# SCH_Flexihal_Direct-Plug_Driver_to_RJ45_.net
KiCad netlist of a schematic drawn in EasyEDA
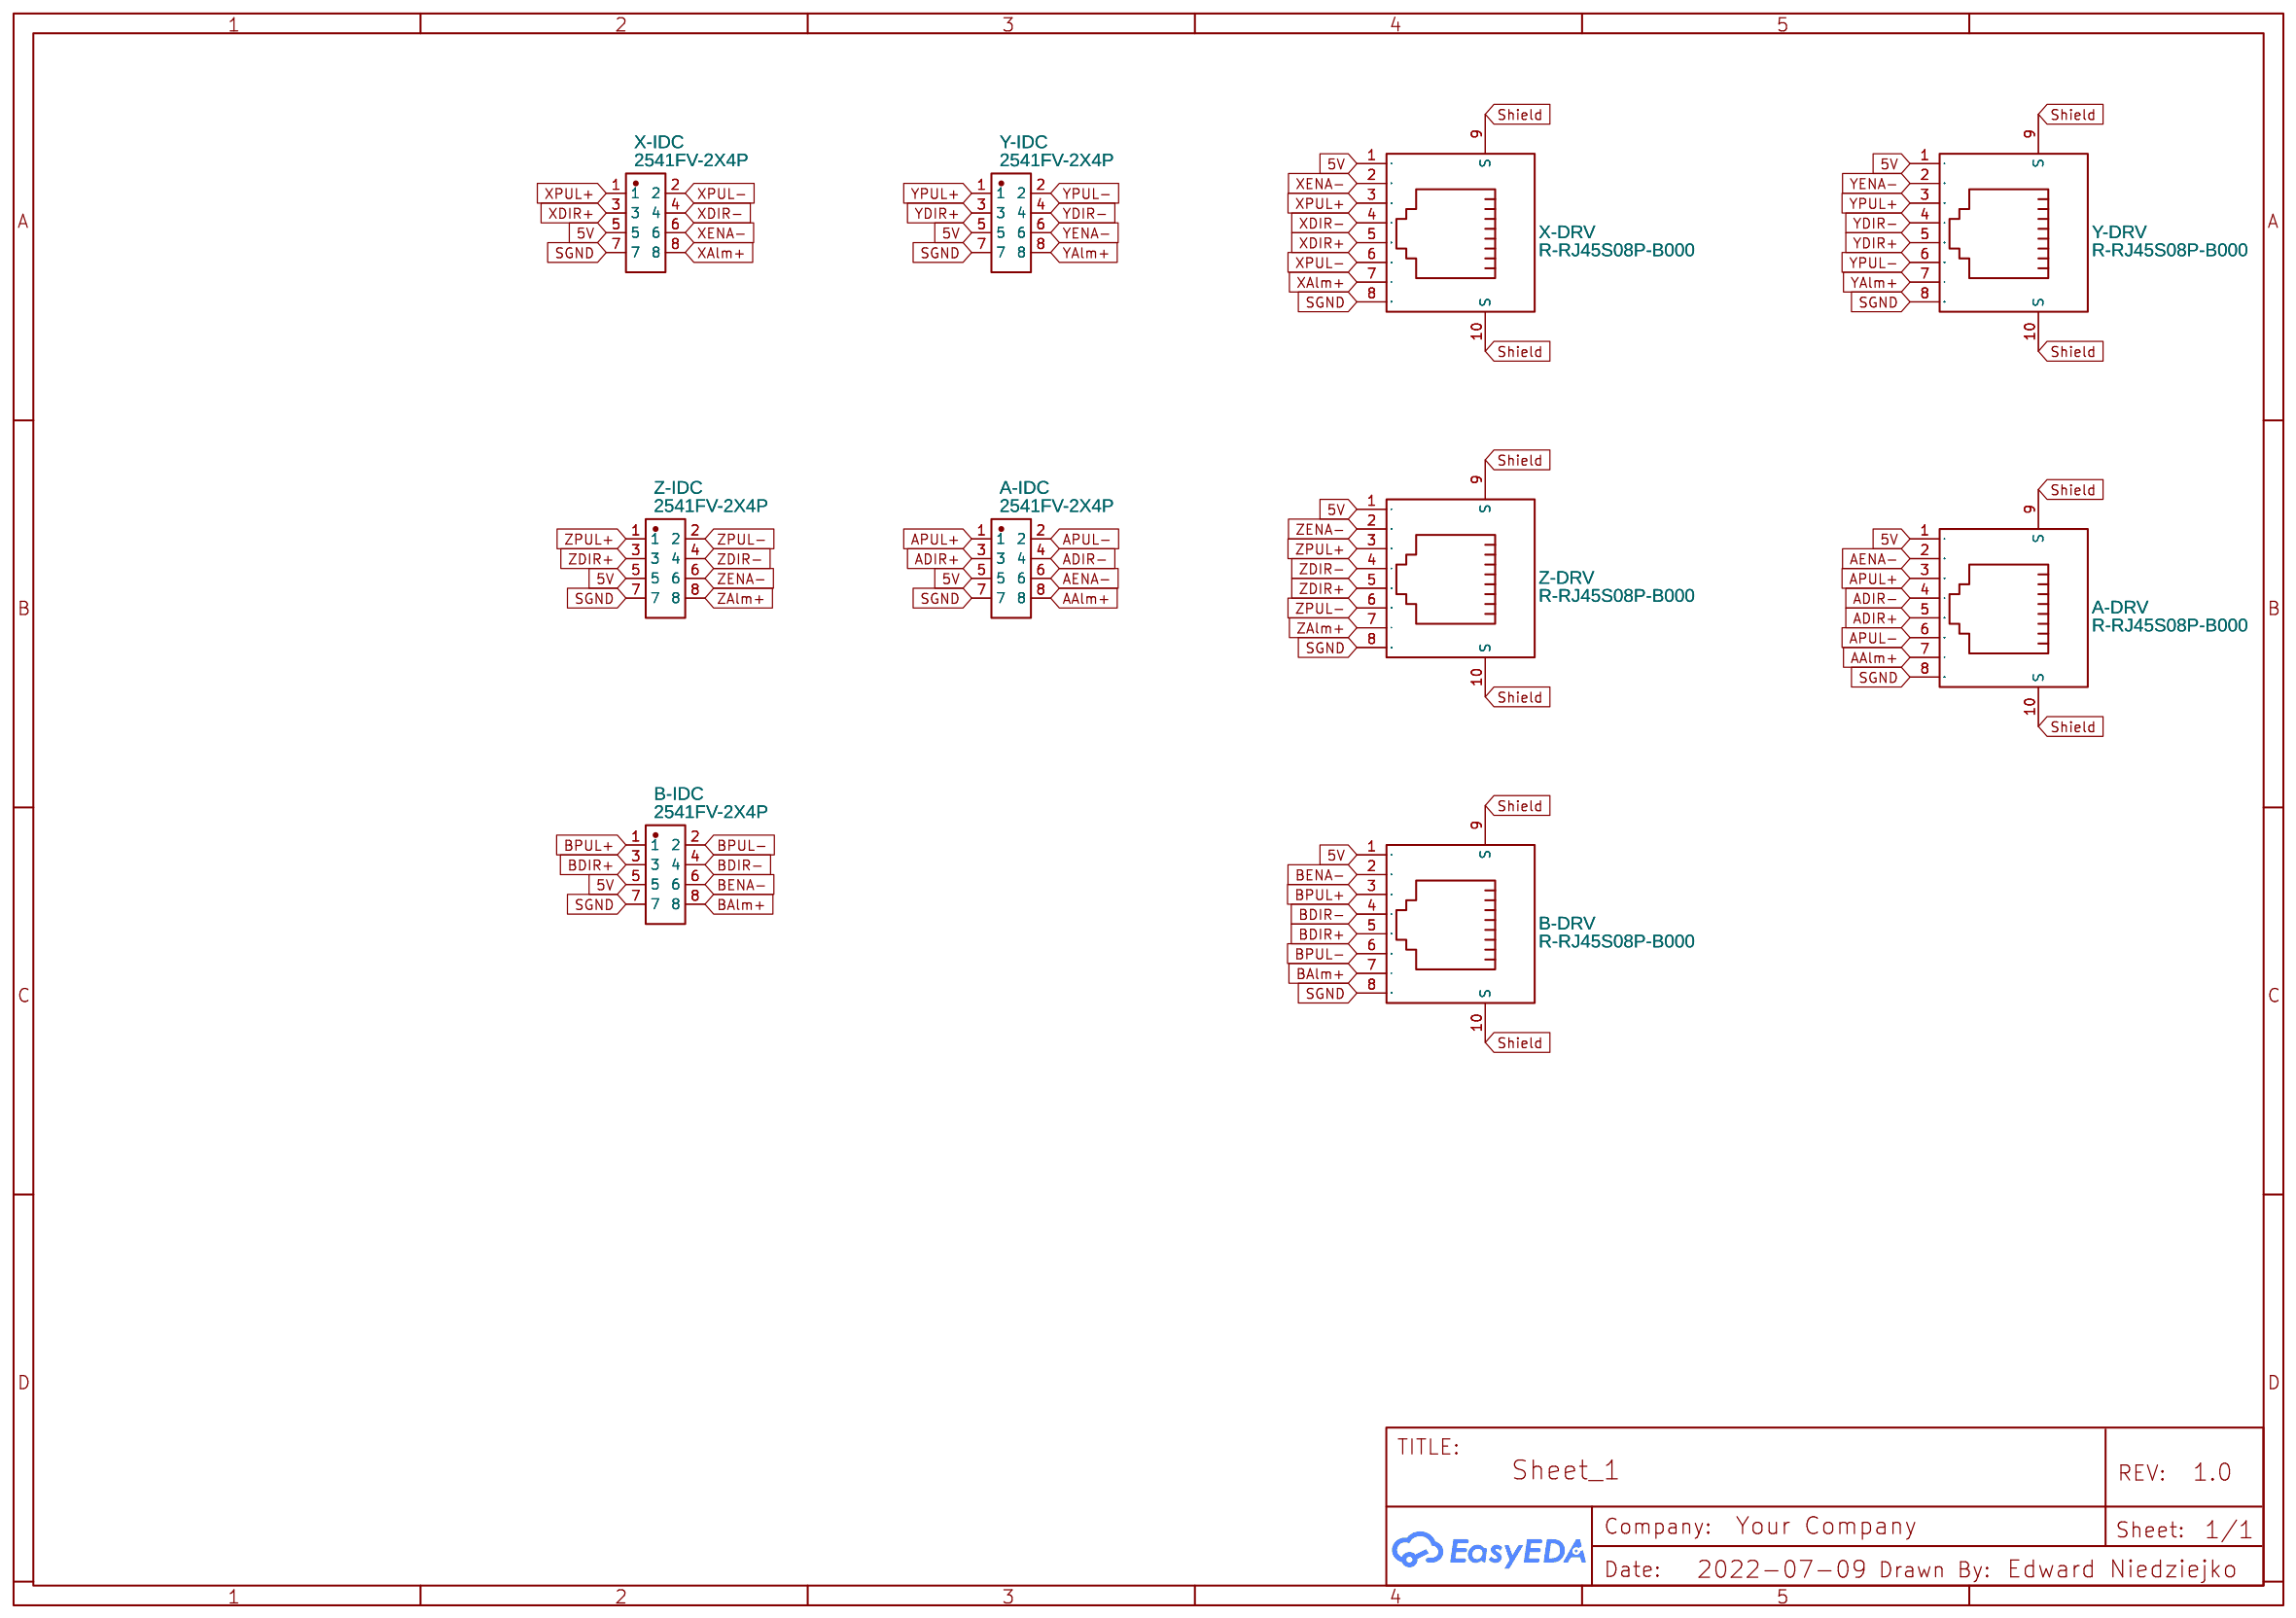
[diagram p0: schematic sheet]

(export (version "E")
  (design (tool "Eeschema 10.0.6"))
  (components
    (comp (ref "A-DRV")
      (value "R-RJ45S08P-B000")
      (fields (field (name "Manufacturer") "Ckmtw(灿科盟)"))
      (libsource (lib "") (part "R-RJ45S08P-B000_4"))
    )
    (comp (ref "A-IDC")
      (value "2541FV-2X4P")
      (fields
        (field (name "Manufacturer Part") "2541FV-2x4P")
        (field (name "Manufacturer") "HanElectricity(瀚源)")
      )
      (libsource (lib "") (part "2541FV-2X4P_2"))
    )
    (comp (ref "B-DRV")
      (value "R-RJ45S08P-B000")
      (fields (field (name "Manufacturer") "Ckmtw(灿科盟)"))
      (libsource (lib "") (part "R-RJ45S08P-B000_2"))
    )
    (comp (ref "B-IDC")
      (value "2541FV-2X4P")
      (fields
        (field (name "Manufacturer Part") "2541FV-2x4P")
        (field (name "Manufacturer") "HanElectricity(瀚源)")
      )
      (libsource (lib "") (part "2541FV-2X4P_1"))
    )
    (comp (ref "X-DRV")
      (value "R-RJ45S08P-B000")
      (fields (field (name "Manufacturer") "Ckmtw(灿科盟)"))
      (libsource (lib "") (part "R-RJ45S08P-B000_3"))
    )
    (comp (ref "X-IDC")
      (value "2541FV-2X4P")
      (fields
        (field (name "Manufacturer Part") "2541FV-2x4P")
        (field (name "Manufacturer") "HanElectricity(瀚源)")
      )
      (libsource (lib "") (part "2541FV-2X4P"))
    )
    (comp (ref "Y-DRV")
      (value "R-RJ45S08P-B000")
      (fields (field (name "Manufacturer") "Ckmtw(灿科盟)"))
      (libsource (lib "") (part "R-RJ45S08P-B000"))
    )
    (comp (ref "Y-IDC")
      (value "2541FV-2X4P")
      (fields
        (field (name "Manufacturer Part") "2541FV-2x4P")
        (field (name "Manufacturer") "HanElectricity(瀚源)")
      )
      (libsource (lib "") (part "2541FV-2X4P_4"))
    )
    (comp (ref "Z-DRV")
      (value "R-RJ45S08P-B000")
      (fields (field (name "Manufacturer") "Ckmtw(灿科盟)"))
      (libsource (lib "") (part "R-RJ45S08P-B000_1"))
    )
    (comp (ref "Z-IDC")
      (value "2541FV-2X4P")
      (fields
        (field (name "Manufacturer Part") "2541FV-2x4P")
        (field (name "Manufacturer") "HanElectricity(瀚源)")
      )
      (libsource (lib "") (part "2541FV-2X4P_3"))
    )
  )
  (nets
    (net (code "1") (name "5V") (class "Default")
      (node (ref "A-DRV") (pin "1") (pinfunction "1_1") (pintype "unspecified"))
      (node (ref "A-IDC") (pin "5") (pinfunction "5_5") (pintype "unspecified"))
      (node (ref "B-DRV") (pin "1") (pinfunction "1_1") (pintype "unspecified"))
      (node (ref "B-IDC") (pin "5") (pinfunction "5_5") (pintype "unspecified"))
      (node (ref "X-DRV") (pin "1") (pinfunction "1_1") (pintype "unspecified"))
      (node (ref "X-IDC") (pin "5") (pinfunction "5_5") (pintype "unspecified"))
      (node (ref "Y-DRV") (pin "1") (pinfunction "1_1") (pintype "unspecified"))
      (node (ref "Y-IDC") (pin "5") (pinfunction "5_5") (pintype "unspecified"))
      (node (ref "Z-DRV") (pin "1") (pinfunction "1_1") (pintype "unspecified"))
      (node (ref "Z-IDC") (pin "5") (pinfunction "5_5") (pintype "unspecified"))
    )
    (net (code "2") (name "AAlm+") (class "Default")
      (node (ref "A-DRV") (pin "7") (pinfunction "7_7") (pintype "unspecified"))
      (node (ref "A-IDC") (pin "8") (pinfunction "8_8") (pintype "unspecified"))
    )
    (net (code "3") (name "ADIR+") (class "Default")
      (node (ref "A-DRV") (pin "5") (pinfunction "5_5") (pintype "unspecified"))
      (node (ref "A-IDC") (pin "3") (pinfunction "3_3") (pintype "unspecified"))
    )
    (net (code "4") (name "ADIR-") (class "Default")
      (node (ref "A-DRV") (pin "4") (pinfunction "4_4") (pintype "unspecified"))
      (node (ref "A-IDC") (pin "4") (pinfunction "4_4") (pintype "unspecified"))
    )
    (net (code "5") (name "AENA-") (class "Default")
      (node (ref "A-DRV") (pin "2") (pinfunction "2_2") (pintype "unspecified"))
      (node (ref "A-IDC") (pin "6") (pinfunction "6_6") (pintype "unspecified"))
    )
    (net (code "6") (name "APUL+") (class "Default")
      (node (ref "A-DRV") (pin "3") (pinfunction "3_3") (pintype "unspecified"))
      (node (ref "A-IDC") (pin "1") (pinfunction "1_1") (pintype "unspecified"))
    )
    (net (code "7") (name "APUL-") (class "Default")
      (node (ref "A-DRV") (pin "6") (pinfunction "6_6") (pintype "unspecified"))
      (node (ref "A-IDC") (pin "2") (pinfunction "2_2") (pintype "unspecified"))
    )
    (net (code "8") (name "BAlm+") (class "Default")
      (node (ref "B-DRV") (pin "7") (pinfunction "7_7") (pintype "unspecified"))
      (node (ref "B-IDC") (pin "8") (pinfunction "8_8") (pintype "unspecified"))
    )
    (net (code "9") (name "BDIR+") (class "Default")
      (node (ref "B-DRV") (pin "5") (pinfunction "5_5") (pintype "unspecified"))
      (node (ref "B-IDC") (pin "3") (pinfunction "3_3") (pintype "unspecified"))
    )
    (net (code "10") (name "BDIR-") (class "Default")
      (node (ref "B-DRV") (pin "4") (pinfunction "4_4") (pintype "unspecified"))
      (node (ref "B-IDC") (pin "4") (pinfunction "4_4") (pintype "unspecified"))
    )
    (net (code "11") (name "BENA-") (class "Default")
      (node (ref "B-DRV") (pin "2") (pinfunction "2_2") (pintype "unspecified"))
      (node (ref "B-IDC") (pin "6") (pinfunction "6_6") (pintype "unspecified"))
    )
    (net (code "12") (name "BPUL+") (class "Default")
      (node (ref "B-DRV") (pin "3") (pinfunction "3_3") (pintype "unspecified"))
      (node (ref "B-IDC") (pin "1") (pinfunction "1_1") (pintype "unspecified"))
    )
    (net (code "13") (name "BPUL-") (class "Default")
      (node (ref "B-DRV") (pin "6") (pinfunction "6_6") (pintype "unspecified"))
      (node (ref "B-IDC") (pin "2") (pinfunction "2_2") (pintype "unspecified"))
    )
    (net (code "14") (name "SGND") (class "Default")
      (node (ref "A-DRV") (pin "8") (pinfunction "8_8") (pintype "unspecified"))
      (node (ref "A-IDC") (pin "7") (pinfunction "7_7") (pintype "unspecified"))
      (node (ref "B-DRV") (pin "8") (pinfunction "8_8") (pintype "unspecified"))
      (node (ref "B-IDC") (pin "7") (pinfunction "7_7") (pintype "unspecified"))
      (node (ref "X-DRV") (pin "8") (pinfunction "8_8") (pintype "unspecified"))
      (node (ref "X-IDC") (pin "7") (pinfunction "7_7") (pintype "unspecified"))
      (node (ref "Y-DRV") (pin "8") (pinfunction "8_8") (pintype "unspecified"))
      (node (ref "Y-IDC") (pin "7") (pinfunction "7_7") (pintype "unspecified"))
      (node (ref "Z-DRV") (pin "8") (pinfunction "8_8") (pintype "unspecified"))
      (node (ref "Z-IDC") (pin "7") (pinfunction "7_7") (pintype "unspecified"))
    )
    (net (code "15") (name "Shield") (class "Default")
      (node (ref "A-DRV") (pin "10") (pinfunction "S_10") (pintype "unspecified"))
      (node (ref "A-DRV") (pin "9") (pinfunction "S_9") (pintype "unspecified"))
      (node (ref "B-DRV") (pin "10") (pinfunction "S_10") (pintype "unspecified"))
      (node (ref "B-DRV") (pin "9") (pinfunction "S_9") (pintype "unspecified"))
      (node (ref "X-DRV") (pin "10") (pinfunction "S_10") (pintype "unspecified"))
      (node (ref "X-DRV") (pin "9") (pinfunction "S_9") (pintype "unspecified"))
      (node (ref "Y-DRV") (pin "10") (pinfunction "S_10") (pintype "unspecified"))
      (node (ref "Y-DRV") (pin "9") (pinfunction "S_9") (pintype "unspecified"))
      (node (ref "Z-DRV") (pin "10") (pinfunction "S_10") (pintype "unspecified"))
      (node (ref "Z-DRV") (pin "9") (pinfunction "S_9") (pintype "unspecified"))
    )
    (net (code "16") (name "XAlm+") (class "Default")
      (node (ref "X-DRV") (pin "7") (pinfunction "7_7") (pintype "unspecified"))
      (node (ref "X-IDC") (pin "8") (pinfunction "8_8") (pintype "unspecified"))
    )
    (net (code "17") (name "XDIR+") (class "Default")
      (node (ref "X-DRV") (pin "5") (pinfunction "5_5") (pintype "unspecified"))
      (node (ref "X-IDC") (pin "3") (pinfunction "3_3") (pintype "unspecified"))
    )
    (net (code "18") (name "XDIR-") (class "Default")
      (node (ref "X-DRV") (pin "4") (pinfunction "4_4") (pintype "unspecified"))
      (node (ref "X-IDC") (pin "4") (pinfunction "4_4") (pintype "unspecified"))
    )
    (net (code "19") (name "XENA-") (class "Default")
      (node (ref "X-DRV") (pin "2") (pinfunction "2_2") (pintype "unspecified"))
      (node (ref "X-IDC") (pin "6") (pinfunction "6_6") (pintype "unspecified"))
    )
    (net (code "20") (name "XPUL+") (class "Default")
      (node (ref "X-DRV") (pin "3") (pinfunction "3_3") (pintype "unspecified"))
      (node (ref "X-IDC") (pin "1") (pinfunction "1_1") (pintype "unspecified"))
    )
    (net (code "21") (name "XPUL-") (class "Default")
      (node (ref "X-DRV") (pin "6") (pinfunction "6_6") (pintype "unspecified"))
      (node (ref "X-IDC") (pin "2") (pinfunction "2_2") (pintype "unspecified"))
    )
    (net (code "22") (name "YAlm+") (class "Default")
      (node (ref "Y-DRV") (pin "7") (pinfunction "7_7") (pintype "unspecified"))
      (node (ref "Y-IDC") (pin "8") (pinfunction "8_8") (pintype "unspecified"))
    )
    (net (code "23") (name "YDIR+") (class "Default")
      (node (ref "Y-DRV") (pin "5") (pinfunction "5_5") (pintype "unspecified"))
      (node (ref "Y-IDC") (pin "3") (pinfunction "3_3") (pintype "unspecified"))
    )
    (net (code "24") (name "YDIR-") (class "Default")
      (node (ref "Y-DRV") (pin "4") (pinfunction "4_4") (pintype "unspecified"))
      (node (ref "Y-IDC") (pin "4") (pinfunction "4_4") (pintype "unspecified"))
    )
    (net (code "25") (name "YENA-") (class "Default")
      (node (ref "Y-DRV") (pin "2") (pinfunction "2_2") (pintype "unspecified"))
      (node (ref "Y-IDC") (pin "6") (pinfunction "6_6") (pintype "unspecified"))
    )
    (net (code "26") (name "YPUL+") (class "Default")
      (node (ref "Y-DRV") (pin "3") (pinfunction "3_3") (pintype "unspecified"))
      (node (ref "Y-IDC") (pin "1") (pinfunction "1_1") (pintype "unspecified"))
    )
    (net (code "27") (name "YPUL-") (class "Default")
      (node (ref "Y-DRV") (pin "6") (pinfunction "6_6") (pintype "unspecified"))
      (node (ref "Y-IDC") (pin "2") (pinfunction "2_2") (pintype "unspecified"))
    )
    (net (code "28") (name "ZAlm+") (class "Default")
      (node (ref "Z-DRV") (pin "7") (pinfunction "7_7") (pintype "unspecified"))
      (node (ref "Z-IDC") (pin "8") (pinfunction "8_8") (pintype "unspecified"))
    )
    (net (code "29") (name "ZDIR+") (class "Default")
      (node (ref "Z-DRV") (pin "5") (pinfunction "5_5") (pintype "unspecified"))
      (node (ref "Z-IDC") (pin "3") (pinfunction "3_3") (pintype "unspecified"))
    )
    (net (code "30") (name "ZDIR-") (class "Default")
      (node (ref "Z-DRV") (pin "4") (pinfunction "4_4") (pintype "unspecified"))
      (node (ref "Z-IDC") (pin "4") (pinfunction "4_4") (pintype "unspecified"))
    )
    (net (code "31") (name "ZENA-") (class "Default")
      (node (ref "Z-DRV") (pin "2") (pinfunction "2_2") (pintype "unspecified"))
      (node (ref "Z-IDC") (pin "6") (pinfunction "6_6") (pintype "unspecified"))
    )
    (net (code "32") (name "ZPUL+") (class "Default")
      (node (ref "Z-DRV") (pin "3") (pinfunction "3_3") (pintype "unspecified"))
      (node (ref "Z-IDC") (pin "1") (pinfunction "1_1") (pintype "unspecified"))
    )
    (net (code "33") (name "ZPUL-") (class "Default")
      (node (ref "Z-DRV") (pin "6") (pinfunction "6_6") (pintype "unspecified"))
      (node (ref "Z-IDC") (pin "2") (pinfunction "2_2") (pintype "unspecified"))
    )
  )
)
